# FaboBoard.net
KiCad netlist of a schematic drawn in EAGLE
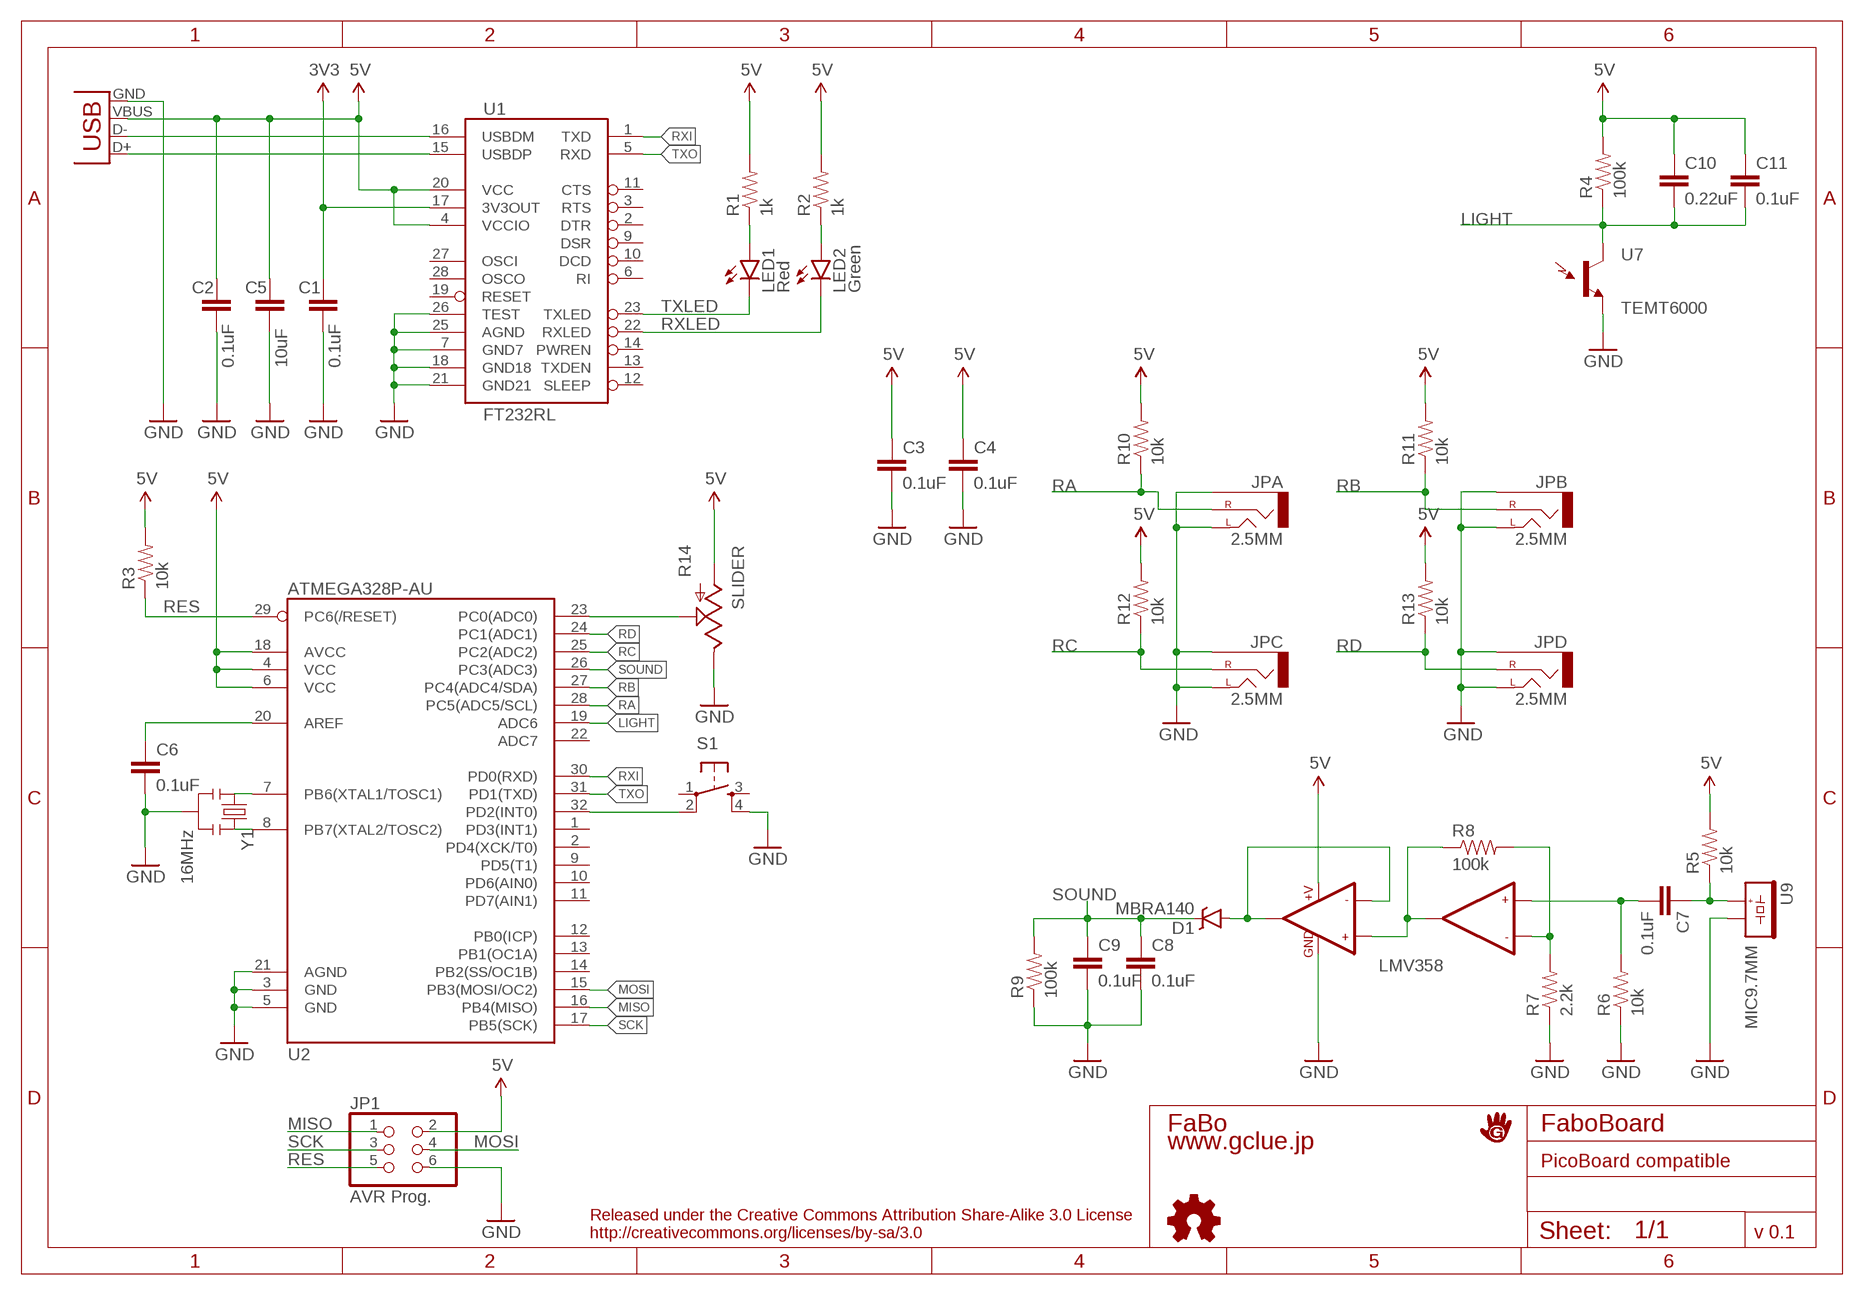
[diagram p0: schematic, sheet 1]

(export (version "E")
  (design (tool "Eeschema 10.0.6"))
  (components
    (comp (ref "C1")
      (value "0.1uF")
      (footprint "eagle-import:EIA0603-CAP")
      (libsource (lib "eagle-import") (part "CAPACITOR0603"))
    )
    (comp (ref "C2")
      (value "0.1uF")
      (footprint "eagle-import:EIA0603-CAP")
      (libsource (lib "eagle-import") (part "CAPACITOR0603"))
    )
    (comp (ref "C3")
      (value "0.1uF")
      (footprint "eagle-import:EIA0603-CAP")
      (libsource (lib "eagle-import") (part "CAPACITOR0603"))
    )
    (comp (ref "C4")
      (value "0.1uF")
      (footprint "eagle-import:EIA0603-CAP")
      (libsource (lib "eagle-import") (part "CAPACITOR0603"))
    )
    (comp (ref "C5")
      (value "10uF")
      (footprint "eagle-import:EIA1206")
      (libsource (lib "eagle-import") (part "CAPACITOR1206"))
    )
    (comp (ref "C6")
      (value "0.1uF")
      (footprint "eagle-import:EIA0603-CAP")
      (libsource (lib "eagle-import") (part "CAPACITOR0603"))
    )
    (comp (ref "C7")
      (value "0.1uF")
      (footprint "eagle-import:EIA0603-CAP")
      (libsource (lib "eagle-import") (part "CAPACITOR0603"))
    )
    (comp (ref "C8")
      (value "0.1uF")
      (footprint "eagle-import:EIA0603-CAP")
      (libsource (lib "eagle-import") (part "CAPACITOR0603"))
    )
    (comp (ref "C9")
      (value "0.1uF")
      (footprint "eagle-import:EIA0603-CAP")
      (libsource (lib "eagle-import") (part "CAPACITOR0603"))
    )
    (comp (ref "C10")
      (value "0.22uF")
      (footprint "eagle-import:EIA0603-CAP")
      (libsource (lib "eagle-import") (part "CAPACITOR0603"))
    )
    (comp (ref "C11")
      (value "0.1uF")
      (footprint "eagle-import:EIA0603-CAP")
      (libsource (lib "eagle-import") (part "CAPACITOR0603"))
    )
    (comp (ref "D1")
      (value "MBRA140")
      (footprint "eagle-import:DIODE-SMA")
      (libsource (lib "eagle-import") (part "MBRA140"))
    )
    (comp (ref "JP1")
      (value "AVR Prog.")
      (footprint "eagle-import:2X03")
      (libsource (lib "eagle-import") (part "PINHD-2X3"))
    )
    (comp (ref "JPA")
      (value "2.5MM")
      (footprint "eagle-import:STEREOJACK_2.5MM_SMD")
      (libsource (lib "eagle-import") (part "STEREOJACK_2.5MM_SMD"))
    )
    (comp (ref "JPB")
      (value "2.5MM")
      (footprint "eagle-import:STEREOJACK_2.5MM_SMD")
      (libsource (lib "eagle-import") (part "STEREOJACK_2.5MM_SMD"))
    )
    (comp (ref "JPC")
      (value "2.5MM")
      (footprint "eagle-import:STEREOJACK_2.5MM_SMD")
      (libsource (lib "eagle-import") (part "STEREOJACK_2.5MM_SMD"))
    )
    (comp (ref "JPD")
      (value "2.5MM")
      (footprint "eagle-import:STEREOJACK_2.5MM_SMD")
      (libsource (lib "eagle-import") (part "STEREOJACK_2.5MM_SMD"))
    )
    (comp (ref "LED1")
      (value "Red")
      (footprint "eagle-import:EIA0603-LED")
      (libsource (lib "eagle-import") (part "LED-EIA0603"))
    )
    (comp (ref "LED2")
      (value "Green")
      (footprint "eagle-import:EIA0603-LED")
      (libsource (lib "eagle-import") (part "LED-EIA0603"))
    )
    (comp (ref "R1")
      (value "1k")
      (footprint "eagle-import:EIA0603-RES")
      (libsource (lib "eagle-import") (part "RESISTOR0603"))
    )
    (comp (ref "R2")
      (value "1k")
      (footprint "eagle-import:EIA0603-RES")
      (libsource (lib "eagle-import") (part "RESISTOR0603"))
    )
    (comp (ref "R3")
      (value "10k")
      (footprint "eagle-import:EIA0603-RES")
      (libsource (lib "eagle-import") (part "RESISTOR0603"))
    )
    (comp (ref "R4")
      (value "100k")
      (footprint "eagle-import:EIA0603-RES")
      (libsource (lib "eagle-import") (part "RESISTOR0603"))
    )
    (comp (ref "R5")
      (value "10k")
      (footprint "eagle-import:EIA0603-RES")
      (libsource (lib "eagle-import") (part "RESISTOR0603"))
    )
    (comp (ref "R6")
      (value "10k")
      (footprint "eagle-import:EIA0603-RES")
      (libsource (lib "eagle-import") (part "RESISTOR0603"))
    )
    (comp (ref "R7")
      (value "2.2k")
      (footprint "eagle-import:EIA0603-RES")
      (libsource (lib "eagle-import") (part "RESISTOR0603"))
    )
    (comp (ref "R8")
      (value "100k")
      (footprint "eagle-import:EIA0603-RES")
      (libsource (lib "eagle-import") (part "RESISTOR0603"))
    )
    (comp (ref "R9")
      (value "100k")
      (footprint "eagle-import:EIA0603-RES")
      (libsource (lib "eagle-import") (part "RESISTOR0603"))
    )
    (comp (ref "R10")
      (value "10k")
      (footprint "eagle-import:EIA0603-RES")
      (libsource (lib "eagle-import") (part "RESISTOR0603"))
    )
    (comp (ref "R11")
      (value "10k")
      (footprint "eagle-import:EIA0603-RES")
      (libsource (lib "eagle-import") (part "RESISTOR0603"))
    )
    (comp (ref "R12")
      (value "10k")
      (footprint "eagle-import:EIA0603-RES")
      (libsource (lib "eagle-import") (part "RESISTOR0603"))
    )
    (comp (ref "R13")
      (value "10k")
      (footprint "eagle-import:EIA0603-RES")
      (libsource (lib "eagle-import") (part "RESISTOR0603"))
    )
    (comp (ref "R14")
      (value "SLIDER")
      (footprint "eagle-import:SLIDER_60MM")
      (libsource (lib "eagle-import") (part "SLIDER60MM"))
    )
    (comp (ref "S1")
      (value "SWITCH-TL3300CF160Q")
      (footprint "eagle-import:TACT-SMD-12MM-TL3300CF160Q")
      (libsource (lib "eagle-import") (part "SWITCH-TL3300CF160Q"))
    )
    (comp (ref "U$2")
      (value "LOGO_GCLUE")
      (footprint "eagle-import:LOGO_GCLUE")
      (libsource (lib "eagle-import") (part "LOGO_GCLUE"))
    )
    (comp (ref "U$3")
      (value "LOGO_OSHW-S")
      (footprint "eagle-import:LOGO_OSHW_S")
      (libsource (lib "eagle-import") (part "LOGO_OSHW-S"))
    )
    (comp (ref "U1")
      (value "FT232RL")
      (footprint "eagle-import:SSOP28")
      (libsource (lib "eagle-import") (part "FT232RL"))
    )
    (comp (ref "U2")
      (value "ATMEGA328P-AU")
      (footprint "eagle-import:TQFP-32-08")
      (libsource (lib "eagle-import") (part "ATMEGA328P-AU"))
    )
    (comp (ref "U7")
      (value "TEMT6000")
      (footprint "eagle-import:TEMT6000")
      (libsource (lib "eagle-import") (part "TEMT6000"))
    )
    (comp (ref "U8")
      (value "LMV358")
      (footprint "eagle-import:SO8-OP")
      (libsource (lib "eagle-import") (part "LMV358"))
    )
    (comp (ref "U9")
      (value "MIC9.7MM")
      (footprint "eagle-import:MIC-ECM")
      (libsource (lib "eagle-import") (part "MIC-ECM"))
    )
    (comp (ref "USB1")
      (value "USBMICRO_SMD")
      (footprint "eagle-import:USB_B_MICRO")
      (libsource (lib "eagle-import") (part "USBMICRO_SMD"))
    )
    (comp (ref "Y1")
      (value "16MHz")
      (footprint "eagle-import:RESONATOR_SMD")
      (libsource (lib "eagle-import") (part "RESONATOR"))
    )
  )
  (nets
    (net (code "1") (name "/RES") (class "Default")
      (node (ref "JP1") (pin "5") (pinfunction "5_5") (pintype "passive"))
      (node (ref "R3") (pin "1") (pinfunction "1_1") (pintype "passive"))
      (node (ref "U2") (pin "29") (pinfunction "PC6(/RESET)_29") (pintype "bidirectional"))
    )
    (net (code "2") (name "/RXLED") (class "Default")
      (node (ref "LED2") (pin "C") (pinfunction "C_C") (pintype "passive"))
      (node (ref "U1") (pin "22") (pinfunction "RXLED_22") (pintype "input"))
    )
    (net (code "3") (name "/TXLED") (class "Default")
      (node (ref "LED1") (pin "C") (pinfunction "C_C") (pintype "passive"))
      (node (ref "U1") (pin "23") (pinfunction "TXLED_23") (pintype "input"))
    )
    (net (code "4") (name "3V3") (class "Default")
      (node (ref "C1") (pin "1") (pinfunction "1_1") (pintype "passive"))
      (node (ref "U1") (pin "17") (pinfunction "3V3OUT_17") (pintype "output"))
    )
    (net (code "5") (name "5V") (class "Default")
      (node (ref "C10") (pin "1") (pinfunction "1_1") (pintype "passive"))
      (node (ref "C11") (pin "1") (pinfunction "1_1") (pintype "passive"))
      (node (ref "C2") (pin "1") (pinfunction "1_1") (pintype "passive"))
      (node (ref "C3") (pin "1") (pinfunction "1_1") (pintype "passive"))
      (node (ref "C4") (pin "1") (pinfunction "1_1") (pintype "passive"))
      (node (ref "C5") (pin "1") (pinfunction "1_1") (pintype "passive"))
      (node (ref "JP1") (pin "2") (pinfunction "2_2") (pintype "passive"))
      (node (ref "R1") (pin "2") (pinfunction "2_2") (pintype "passive"))
      (node (ref "R10") (pin "2") (pinfunction "2_2") (pintype "passive"))
      (node (ref "R11") (pin "2") (pinfunction "2_2") (pintype "passive"))
      (node (ref "R12") (pin "2") (pinfunction "2_2") (pintype "passive"))
      (node (ref "R13") (pin "2") (pinfunction "2_2") (pintype "passive"))
      (node (ref "R14") (pin "3") (pinfunction "3_3") (pintype "passive"))
      (node (ref "R2") (pin "2") (pinfunction "2_2") (pintype "passive"))
      (node (ref "R3") (pin "2") (pinfunction "2_2") (pintype "passive"))
      (node (ref "R4") (pin "2") (pinfunction "2_2") (pintype "passive"))
      (node (ref "R5") (pin "2") (pinfunction "2_2") (pintype "passive"))
      (node (ref "U1") (pin "20") (pinfunction "VCC_20") (pintype "power_in"))
      (node (ref "U1") (pin "4") (pinfunction "VCCIO_4") (pintype "power_in"))
      (node (ref "U2") (pin "18") (pinfunction "AVCC_18") (pintype "bidirectional"))
      (node (ref "U2") (pin "4") (pinfunction "VCC_4") (pintype "bidirectional"))
      (node (ref "U2") (pin "6") (pinfunction "VCC_6") (pintype "bidirectional"))
      (node (ref "U8") (pin "8") (pinfunction "+V_8") (pintype "power_in"))
      (node (ref "USB1") (pin "VBUS") (pinfunction "VBUS_VBUS") (pintype "bidirectional"))
    )
    (net (code "6") (name "GND") (class "Default")
      (node (ref "C1") (pin "2") (pinfunction "2_2") (pintype "passive"))
      (node (ref "C2") (pin "2") (pinfunction "2_2") (pintype "passive"))
      (node (ref "C3") (pin "2") (pinfunction "2_2") (pintype "passive"))
      (node (ref "C4") (pin "2") (pinfunction "2_2") (pintype "passive"))
      (node (ref "C5") (pin "2") (pinfunction "2_2") (pintype "passive"))
      (node (ref "C6") (pin "2") (pinfunction "2_2") (pintype "passive"))
      (node (ref "C8") (pin "2") (pinfunction "2_2") (pintype "passive"))
      (node (ref "C9") (pin "2") (pinfunction "2_2") (pintype "passive"))
      (node (ref "JP1") (pin "6") (pinfunction "6_6") (pintype "passive"))
      (node (ref "JPA") (pin "1") (pinfunction "LEFT_1") (pintype "bidirectional"))
      (node (ref "JPA") (pin "5") (pinfunction "SLEEVE_5") (pintype "bidirectional"))
      (node (ref "JPB") (pin "1") (pinfunction "LEFT_1") (pintype "bidirectional"))
      (node (ref "JPB") (pin "5") (pinfunction "SLEEVE_5") (pintype "bidirectional"))
      (node (ref "JPC") (pin "1") (pinfunction "LEFT_1") (pintype "bidirectional"))
      (node (ref "JPC") (pin "5") (pinfunction "SLEEVE_5") (pintype "bidirectional"))
      (node (ref "JPD") (pin "1") (pinfunction "LEFT_1") (pintype "bidirectional"))
      (node (ref "JPD") (pin "5") (pinfunction "SLEEVE_5") (pintype "bidirectional"))
      (node (ref "R14") (pin "1") (pinfunction "1_1") (pintype "passive"))
      (node (ref "R6") (pin "1") (pinfunction "1_1") (pintype "passive"))
      (node (ref "R7") (pin "1") (pinfunction "1_1") (pintype "passive"))
      (node (ref "R9") (pin "1") (pinfunction "1_1") (pintype "passive"))
      (node (ref "S1") (pin "4") (pinfunction "4_4") (pintype "passive"))
      (node (ref "U1") (pin "18") (pinfunction "GND18_18") (pintype "power_in"))
      (node (ref "U1") (pin "21") (pinfunction "GND21_21") (pintype "power_in"))
      (node (ref "U1") (pin "25") (pinfunction "AGND_25") (pintype "power_in"))
      (node (ref "U1") (pin "26") (pinfunction "TEST_26") (pintype "input"))
      (node (ref "U1") (pin "7") (pinfunction "GND7_7") (pintype "power_in"))
      (node (ref "U2") (pin "21") (pinfunction "AGND_21") (pintype "bidirectional"))
      (node (ref "U2") (pin "3") (pinfunction "GND_3") (pintype "bidirectional"))
      (node (ref "U2") (pin "5") (pinfunction "GND_5") (pintype "bidirectional"))
      (node (ref "U7") (pin "EMITTER") (pinfunction "E1_EMITTER") (pintype "passive"))
      (node (ref "U8") (pin "4") (pinfunction "GND_4") (pintype "power_in"))
      (node (ref "U9") (pin "-") (pinfunction "-_-") (pintype "passive"))
      (node (ref "USB1") (pin "GND") (pinfunction "GND_GND") (pintype "bidirectional"))
      (node (ref "Y1") (pin "2") (pinfunction "2_2") (pintype "passive"))
    )
    (net (code "7") (name "LIGHT") (class "Default")
      (node (ref "C10") (pin "2") (pinfunction "2_2") (pintype "passive"))
      (node (ref "C11") (pin "2") (pinfunction "2_2") (pintype "passive"))
      (node (ref "R4") (pin "1") (pinfunction "1_1") (pintype "passive"))
      (node (ref "U2") (pin "19") (pinfunction "ADC6_19") (pintype "bidirectional"))
      (node (ref "U7") (pin "COLLECTOR") (pinfunction "C1_COLLECTOR") (pintype "passive"))
    )
    (net (code "8") (name "MISO") (class "Default")
      (node (ref "JP1") (pin "1") (pinfunction "1_1") (pintype "passive"))
      (node (ref "U2") (pin "16") (pinfunction "PB4(MISO)_16") (pintype "bidirectional"))
    )
    (net (code "9") (name "MOSI") (class "Default")
      (node (ref "JP1") (pin "4") (pinfunction "4_4") (pintype "passive"))
      (node (ref "U2") (pin "15") (pinfunction "PB3(MOSI/OC2)_15") (pintype "bidirectional"))
    )
    (net (code "10") (name "Net-(C7-Pad1)") (class "Default")
      (node (ref "C7") (pin "1") (pinfunction "1_1") (pintype "passive"))
      (node (ref "R5") (pin "1") (pinfunction "1_1") (pintype "passive"))
      (node (ref "U9") (pin "+") (pinfunction "+_+") (pintype "passive"))
    )
    (net (code "11") (name "Net-(LED1-PadA)") (class "Default")
      (node (ref "LED1") (pin "A") (pinfunction "A_A") (pintype "passive"))
      (node (ref "R1") (pin "1") (pinfunction "1_1") (pintype "passive"))
    )
    (net (code "12") (name "Net-(LED2-PadA)") (class "Default")
      (node (ref "LED2") (pin "A") (pinfunction "A_A") (pintype "passive"))
      (node (ref "R2") (pin "1") (pinfunction "1_1") (pintype "passive"))
    )
    (net (code "13") (name "Net-(U1-USBDM)") (class "Default")
      (node (ref "U1") (pin "16") (pinfunction "USBDM_16") (pintype "bidirectional"))
      (node (ref "USB1") (pin "D-") (pinfunction "D-_D-") (pintype "bidirectional"))
    )
    (net (code "14") (name "Net-(U1-USBDP)") (class "Default")
      (node (ref "U1") (pin "15") (pinfunction "USBDP_15") (pintype "bidirectional"))
      (node (ref "USB1") (pin "D+") (pinfunction "D+_D+") (pintype "bidirectional"))
    )
    (net (code "15") (name "Net-(U2-AREF)") (class "Default")
      (node (ref "C6") (pin "1") (pinfunction "1_1") (pintype "passive"))
      (node (ref "U2") (pin "20") (pinfunction "AREF_20") (pintype "bidirectional"))
    )
    (net (code "16") (name "Net-(U2-PB6(XTAL1{slash}TOSC1))") (class "Default")
      (node (ref "U2") (pin "7") (pinfunction "PB6(XTAL1/TOSC1)_7") (pintype "bidirectional"))
      (node (ref "Y1") (pin "1") (pinfunction "1_1") (pintype "passive"))
    )
    (net (code "17") (name "Net-(U2-PB7(XTAL2{slash}TOSC2))") (class "Default")
      (node (ref "U2") (pin "8") (pinfunction "PB7(XTAL2/TOSC2)_8") (pintype "bidirectional"))
      (node (ref "Y1") (pin "3") (pinfunction "3_3") (pintype "passive"))
    )
    (net (code "18") (name "Net-(U2-PC0(ADC0))") (class "Default")
      (node (ref "R14") (pin "2") (pinfunction "2_2") (pintype "passive"))
      (node (ref "U2") (pin "23") (pinfunction "PC0(ADC0)_23") (pintype "bidirectional"))
    )
    (net (code "19") (name "Net-(U2-PD2(INT0))") (class "Default")
      (node (ref "S1") (pin "2") (pinfunction "2_2") (pintype "passive"))
      (node (ref "U2") (pin "32") (pinfunction "PD2(INT0)_32") (pintype "bidirectional"))
    )
    (net (code "20") (name "Net-(U8A-+IN1)") (class "Default")
      (node (ref "R8") (pin "1") (pinfunction "1_1") (pintype "passive"))
      (node (ref "U8") (pin "3") (pinfunction "+IN1_3") (pintype "input"))
      (node (ref "U8") (pin "7") (pinfunction "OUT2_7") (pintype "output"))
    )
    (net (code "21") (name "Net-(U8A--IN1)") (class "Default")
      (node (ref "D1") (pin "A") (pinfunction "A_A") (pintype "passive"))
      (node (ref "U8") (pin "1") (pinfunction "OUT1_1") (pintype "output"))
      (node (ref "U8") (pin "2") (pinfunction "-IN1_2") (pintype "input"))
    )
    (net (code "22") (name "Net-(U8B-+IN2)") (class "Default")
      (node (ref "C7") (pin "2") (pinfunction "2_2") (pintype "passive"))
      (node (ref "R6") (pin "2") (pinfunction "2_2") (pintype "passive"))
      (node (ref "U8") (pin "5") (pinfunction "+IN2_5") (pintype "input"))
    )
    (net (code "23") (name "Net-(U8B--IN2)") (class "Default")
      (node (ref "R7") (pin "2") (pinfunction "2_2") (pintype "passive"))
      (node (ref "R8") (pin "2") (pinfunction "2_2") (pintype "passive"))
      (node (ref "U8") (pin "6") (pinfunction "-IN2_6") (pintype "input"))
    )
    (net (code "24") (name "RA") (class "Default")
      (node (ref "JPA") (pin "4") (pinfunction "RIGHT_4") (pintype "bidirectional"))
      (node (ref "R10") (pin "1") (pinfunction "1_1") (pintype "passive"))
      (node (ref "U2") (pin "28") (pinfunction "PC5(ADC5/SCL)_28") (pintype "bidirectional"))
    )
    (net (code "25") (name "RB") (class "Default")
      (node (ref "JPB") (pin "4") (pinfunction "RIGHT_4") (pintype "bidirectional"))
      (node (ref "R11") (pin "1") (pinfunction "1_1") (pintype "passive"))
      (node (ref "U2") (pin "27") (pinfunction "PC4(ADC4/SDA)_27") (pintype "bidirectional"))
    )
    (net (code "26") (name "RC") (class "Default")
      (node (ref "JPC") (pin "4") (pinfunction "RIGHT_4") (pintype "bidirectional"))
      (node (ref "R12") (pin "1") (pinfunction "1_1") (pintype "passive"))
      (node (ref "U2") (pin "25") (pinfunction "PC2(ADC2)_25") (pintype "bidirectional"))
    )
    (net (code "27") (name "RD") (class "Default")
      (node (ref "JPD") (pin "4") (pinfunction "RIGHT_4") (pintype "bidirectional"))
      (node (ref "R13") (pin "1") (pinfunction "1_1") (pintype "passive"))
      (node (ref "U2") (pin "24") (pinfunction "PC1(ADC1)_24") (pintype "bidirectional"))
    )
    (net (code "28") (name "RXI") (class "Default")
      (node (ref "U1") (pin "1") (pinfunction "TXD_1") (pintype "output"))
      (node (ref "U2") (pin "30") (pinfunction "PD0(RXD)_30") (pintype "bidirectional"))
    )
    (net (code "29") (name "SCK") (class "Default")
      (node (ref "JP1") (pin "3") (pinfunction "3_3") (pintype "passive"))
      (node (ref "U2") (pin "17") (pinfunction "PB5(SCK)_17") (pintype "bidirectional"))
    )
    (net (code "30") (name "SOUND") (class "Default")
      (node (ref "C8") (pin "1") (pinfunction "1_1") (pintype "passive"))
      (node (ref "C9") (pin "1") (pinfunction "1_1") (pintype "passive"))
      (node (ref "D1") (pin "C") (pinfunction "C_C") (pintype "passive"))
      (node (ref "R9") (pin "2") (pinfunction "2_2") (pintype "passive"))
      (node (ref "U2") (pin "26") (pinfunction "PC3(ADC3)_26") (pintype "bidirectional"))
    )
    (net (code "31") (name "TXO") (class "Default")
      (node (ref "U1") (pin "5") (pinfunction "RXD_5") (pintype "input"))
      (node (ref "U2") (pin "31") (pinfunction "PD1(TXD)_31") (pintype "bidirectional"))
    )
    (net (code "32") (name "unconnected-(S1-Pad1)") (class "Default")
      (node (ref "S1") (pin "1") (pinfunction "1_1") (pintype "passive"))
    )
    (net (code "33") (name "unconnected-(S1-Pad3)") (class "Default")
      (node (ref "S1") (pin "3") (pinfunction "3_3") (pintype "passive"))
    )
    (net (code "34") (name "unconnected-(U1-CTS-Pad11)") (class "Default")
      (node (ref "U1") (pin "11") (pinfunction "CTS_11") (pintype "input"))
    )
    (net (code "35") (name "unconnected-(U1-DCD-Pad10)") (class "Default")
      (node (ref "U1") (pin "10") (pinfunction "DCD_10") (pintype "input"))
    )
    (net (code "36") (name "unconnected-(U1-DSR-Pad9)") (class "Default")
      (node (ref "U1") (pin "9") (pinfunction "DSR_9") (pintype "input"))
    )
    (net (code "37") (name "unconnected-(U1-DTR-Pad2)") (class "Default")
      (node (ref "U1") (pin "2") (pinfunction "DTR_2") (pintype "output"))
    )
    (net (code "38") (name "unconnected-(U1-OSCI-Pad27)") (class "Default")
      (node (ref "U1") (pin "27") (pinfunction "OSCI_27") (pintype "input"))
    )
    (net (code "39") (name "unconnected-(U1-OSCO-Pad28)") (class "Default")
      (node (ref "U1") (pin "28") (pinfunction "OSCO_28") (pintype "output"))
    )
    (net (code "40") (name "unconnected-(U1-PWREN-Pad14)") (class "Default")
      (node (ref "U1") (pin "14") (pinfunction "PWREN_14") (pintype "input"))
    )
    (net (code "41") (name "unconnected-(U1-RESET-Pad19)") (class "Default")
      (node (ref "U1") (pin "19") (pinfunction "RESET_19") (pintype "input"))
    )
    (net (code "42") (name "unconnected-(U1-RI-Pad6)") (class "Default")
      (node (ref "U1") (pin "6") (pinfunction "RI_6") (pintype "input"))
    )
    (net (code "43") (name "unconnected-(U1-RTS-Pad3)") (class "Default")
      (node (ref "U1") (pin "3") (pinfunction "RTS_3") (pintype "output"))
    )
    (net (code "44") (name "unconnected-(U1-SLEEP-Pad12)") (class "Default")
      (node (ref "U1") (pin "12") (pinfunction "SLEEP_12") (pintype "input"))
    )
    (net (code "45") (name "unconnected-(U1-TXDEN-Pad13)") (class "Default")
      (node (ref "U1") (pin "13") (pinfunction "TXDEN_13") (pintype "input"))
    )
    (net (code "46") (name "unconnected-(U2-ADC7-Pad22)") (class "Default")
      (node (ref "U2") (pin "22") (pinfunction "ADC7_22") (pintype "bidirectional"))
    )
    (net (code "47") (name "unconnected-(U2-PB0(ICP)-Pad12)") (class "Default")
      (node (ref "U2") (pin "12") (pinfunction "PB0(ICP)_12") (pintype "bidirectional"))
    )
    (net (code "48") (name "unconnected-(U2-PB1(OC1A)-Pad13)") (class "Default")
      (node (ref "U2") (pin "13") (pinfunction "PB1(OC1A)_13") (pintype "bidirectional"))
    )
    (net (code "49") (name "unconnected-(U2-PB2(SS{slash}OC1B)-Pad14)") (class "Default")
      (node (ref "U2") (pin "14") (pinfunction "PB2(SS/OC1B)_14") (pintype "bidirectional"))
    )
    (net (code "50") (name "unconnected-(U2-PD3(INT1)-Pad1)") (class "Default")
      (node (ref "U2") (pin "1") (pinfunction "PD3(INT1)_1") (pintype "bidirectional"))
    )
    (net (code "51") (name "unconnected-(U2-PD4(XCK{slash}T0)-Pad2)") (class "Default")
      (node (ref "U2") (pin "2") (pinfunction "PD4(XCK/T0)_2") (pintype "bidirectional"))
    )
    (net (code "52") (name "unconnected-(U2-PD5(T1)-Pad9)") (class "Default")
      (node (ref "U2") (pin "9") (pinfunction "PD5(T1)_9") (pintype "bidirectional"))
    )
    (net (code "53") (name "unconnected-(U2-PD6(AIN0)-Pad10)") (class "Default")
      (node (ref "U2") (pin "10") (pinfunction "PD6(AIN0)_10") (pintype "bidirectional"))
    )
    (net (code "54") (name "unconnected-(U2-PD7(AIN1)-Pad11)") (class "Default")
      (node (ref "U2") (pin "11") (pinfunction "PD7(AIN1)_11") (pintype "bidirectional"))
    )
  )
)
